# MPU6050.net
KiCad netlist of a schematic drawn in EAGLE
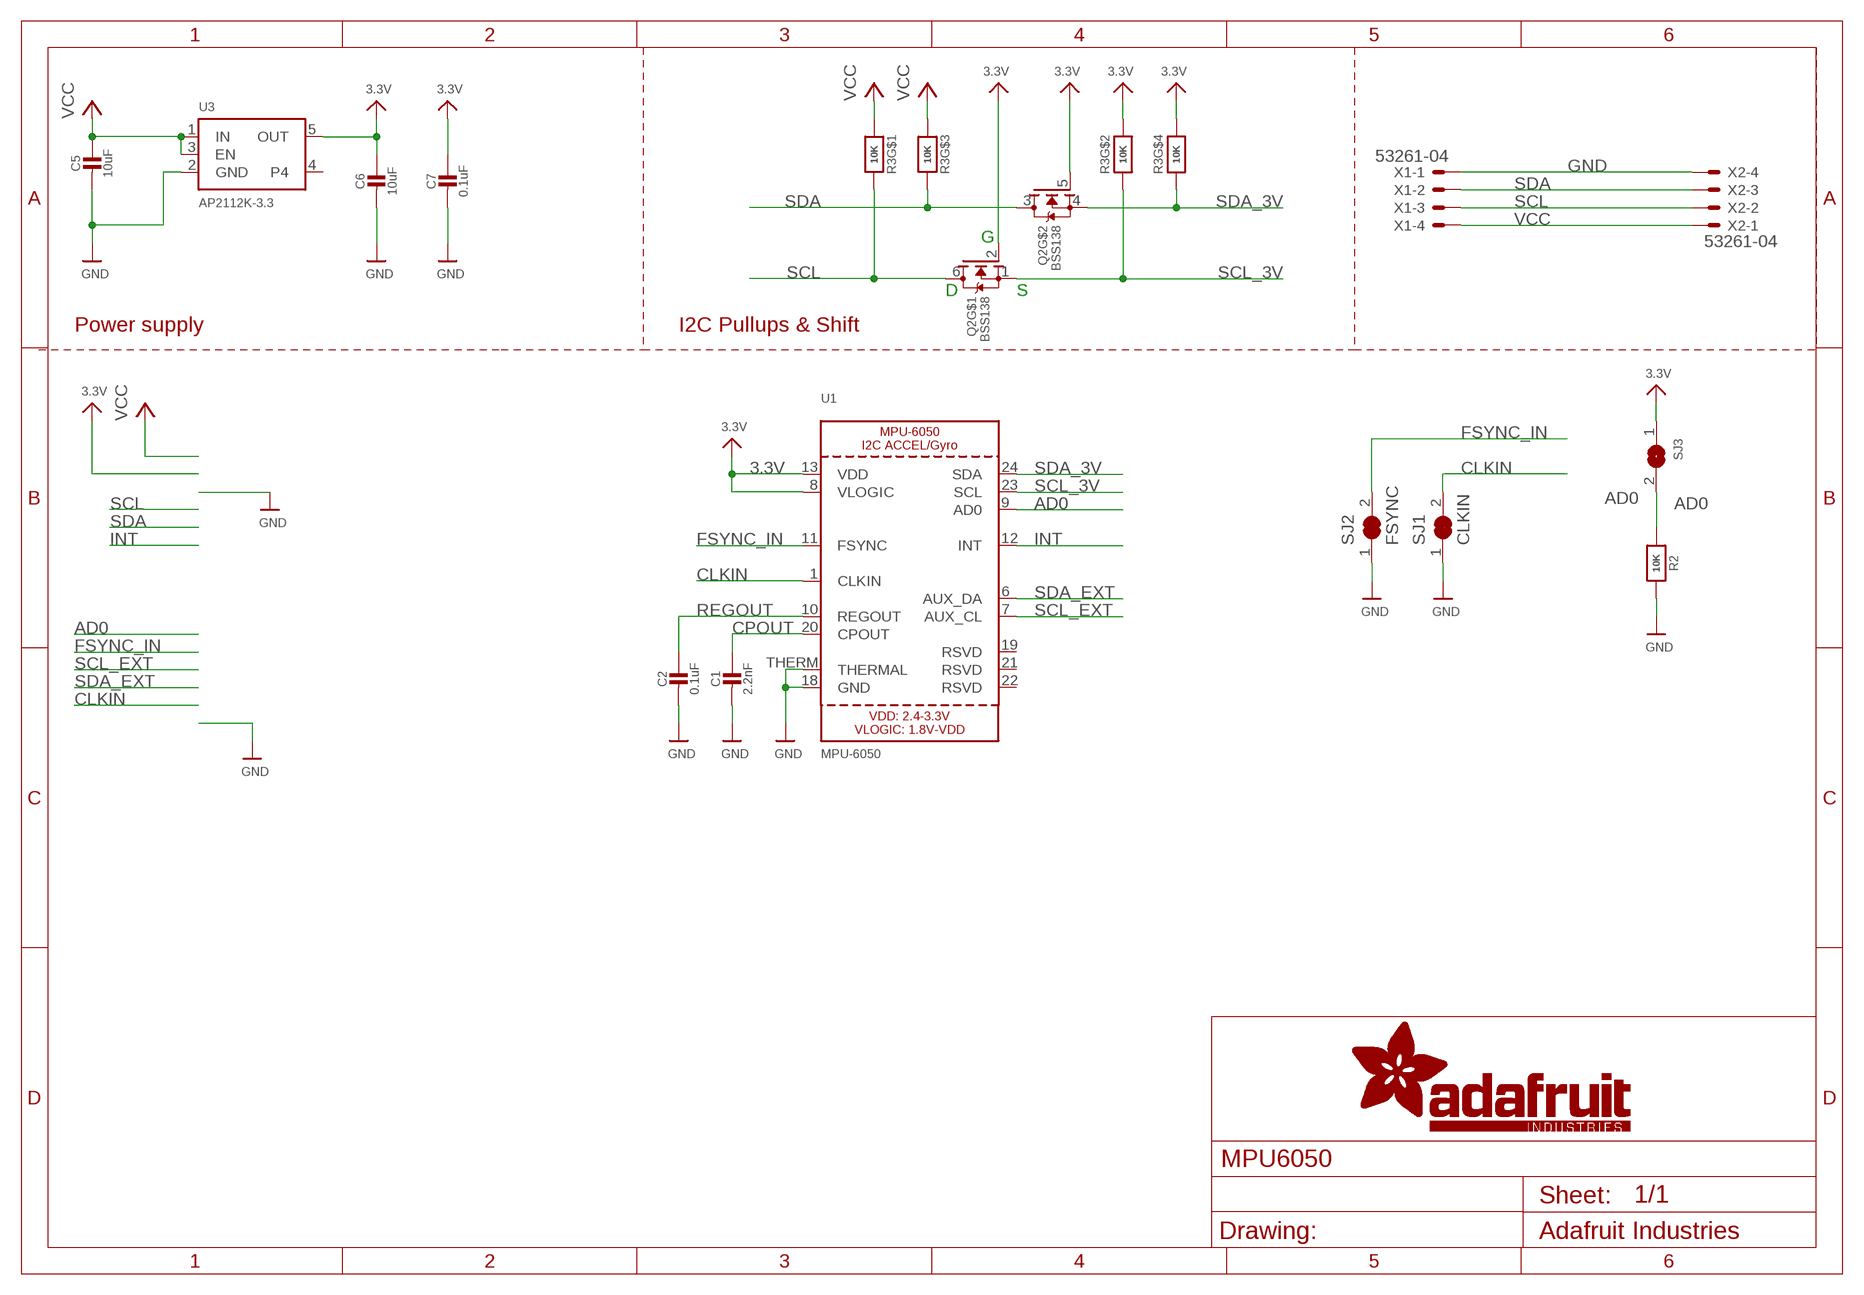
[diagram p0: schematic, sheet 1]

(export (version "E")
  (design (tool "Eeschema 10.0.6"))
  (components
    (comp (ref "C1")
      (value "2.2nF")
      (footprint "eagle-import:0603-NO")
      (libsource (lib "eagle-import") (part "CAP_CERAMIC0603_NO"))
    )
    (comp (ref "C2")
      (value "0.1uF")
      (footprint "eagle-import:0603-NO")
      (libsource (lib "eagle-import") (part "CAP_CERAMIC0603_NO"))
    )
    (comp (ref "C5")
      (value "10uF")
      (footprint "eagle-import:0805-NO")
      (libsource (lib "eagle-import") (part "CAP_CERAMIC0805-NOOUTLINE"))
    )
    (comp (ref "C6")
      (value "10uF")
      (footprint "eagle-import:0805-NO")
      (libsource (lib "eagle-import") (part "CAP_CERAMIC0805-NOOUTLINE"))
    )
    (comp (ref "C7")
      (value "0.1uF")
      (footprint "eagle-import:0603-NO")
      (libsource (lib "eagle-import") (part "CAP_CERAMIC0603_NO"))
    )
    (comp (ref "Q2")
      (value "BSS138")
      (footprint "eagle-import:SOT363")
      (libsource (lib "eagle-import") (part "MOSFET-N_DUAL"))
    )
    (comp (ref "R2")
      (value "10K")
      (footprint "eagle-import:0603-NO")
      (libsource (lib "eagle-import") (part "RESISTOR_0603_NOOUT"))
    )
    (comp (ref "R3")
      (value "10K")
      (footprint "eagle-import:RESPACK_4X0603")
      (libsource (lib "eagle-import") (part "RESISTOR_4PACK"))
    )
    (comp (ref "SJ1")
      (value "CLKIN")
      (footprint "eagle-import:SOLDERJUMPER_CLOSEDWIRE")
      (libsource (lib "eagle-import") (part "SOLDERJUMPER_CLOSED"))
    )
    (comp (ref "SJ2")
      (value "FSYNC")
      (footprint "eagle-import:SOLDERJUMPER_CLOSEDWIRE")
      (libsource (lib "eagle-import") (part "SOLDERJUMPER_CLOSED"))
    )
    (comp (ref "SJ3")
      (value "SOLDERJUMPER")
      (footprint "eagle-import:SOLDERJUMPER_ARROW_NOPASTE")
      (libsource (lib "eagle-import") (part "SOLDERJUMPER"))
    )
    (comp (ref "U1")
      (value "MPU-6050")
      (footprint "eagle-import:QFN24_4MM_SMSC")
      (libsource (lib "eagle-import") (part "MPU-6050"))
    )
    (comp (ref "U3")
      (value "AP2112K-3.3")
      (footprint "eagle-import:SOT23-5")
      (libsource (lib "eagle-import") (part "VREG_SOT23-5"))
    )
    (comp (ref "X1")
      (value "53261-04")
      (footprint "eagle-import:53261-04")
      (fields (field (name "MF") "MOLEX"))
      (libsource (lib "eagle-import") (part "53?-04261"))
    )
    (comp (ref "X2")
      (value "53261-04")
      (footprint "eagle-import:53261-04")
      (fields (field (name "MF") "MOLEX"))
      (libsource (lib "eagle-import") (part "53?-04261"))
    )
  )
  (nets
    (net (code "1") (name "/AD0") (class "Default")
      (node (ref "R2") (pin "1") (pinfunction "1_1") (pintype "passive"))
      (node (ref "SJ3") (pin "2") (pinfunction "2_2") (pintype "passive"))
      (node (ref "U1") (pin "9") (pinfunction "AD0_9") (pintype "input"))
    )
    (net (code "2") (name "/CLKIN") (class "Default")
      (node (ref "SJ1") (pin "2") (pinfunction "2_2") (pintype "passive"))
      (node (ref "U1") (pin "1") (pinfunction "CLKIN_1") (pintype "input"))
    )
    (net (code "3") (name "/CPOUT") (class "Default")
      (node (ref "C1") (pin "1") (pinfunction "1_1") (pintype "passive"))
      (node (ref "U1") (pin "20") (pinfunction "CPOUT_20") (pintype "passive"))
    )
    (net (code "4") (name "/FSYNC_IN") (class "Default")
      (node (ref "SJ2") (pin "2") (pinfunction "2_2") (pintype "passive"))
      (node (ref "U1") (pin "11") (pinfunction "FSYNC_11") (pintype "input"))
    )
    (net (code "5") (name "/INT") (class "Default")
      (node (ref "U1") (pin "12") (pinfunction "INT_12") (pintype "output"))
    )
    (net (code "6") (name "/REGOUT") (class "Default")
      (node (ref "C2") (pin "1") (pinfunction "1_1") (pintype "passive"))
      (node (ref "U1") (pin "10") (pinfunction "REGOUT_10") (pintype "passive"))
    )
    (net (code "7") (name "/SCL") (class "Default")
      (node (ref "Q2") (pin "6") (pinfunction "D_6") (pintype "bidirectional"))
      (node (ref "R3") (pin "8") (pinfunction "2_8") (pintype "passive"))
      (node (ref "X1") (pin "3") (pinfunction "S_3") (pintype "passive"))
      (node (ref "X2") (pin "2") (pinfunction "S_2") (pintype "passive"))
    )
    (net (code "8") (name "/SCL_3V") (class "Default")
      (node (ref "Q2") (pin "1") (pinfunction "S_1") (pintype "bidirectional"))
      (node (ref "R3") (pin "7") (pinfunction "2_7") (pintype "passive"))
      (node (ref "U1") (pin "23") (pinfunction "SCL_23") (pintype "bidirectional"))
    )
    (net (code "9") (name "/SCL_EXT") (class "Default")
      (node (ref "U1") (pin "7") (pinfunction "AUX_CL_7") (pintype "bidirectional"))
    )
    (net (code "10") (name "/SDA") (class "Default")
      (node (ref "Q2") (pin "3") (pinfunction "D_3") (pintype "bidirectional"))
      (node (ref "R3") (pin "6") (pinfunction "2_6") (pintype "passive"))
      (node (ref "X1") (pin "2") (pinfunction "S_2") (pintype "passive"))
      (node (ref "X2") (pin "3") (pinfunction "S_3") (pintype "passive"))
    )
    (net (code "11") (name "/SDA_3V") (class "Default")
      (node (ref "Q2") (pin "4") (pinfunction "S_4") (pintype "bidirectional"))
      (node (ref "R3") (pin "5") (pinfunction "2_5") (pintype "passive"))
      (node (ref "U1") (pin "24") (pinfunction "SDA_24") (pintype "bidirectional"))
    )
    (net (code "12") (name "/SDA_EXT") (class "Default")
      (node (ref "U1") (pin "6") (pinfunction "AUX_DA_6") (pintype "bidirectional"))
    )
    (net (code "13") (name "3.3V") (class "Default")
      (node (ref "C6") (pin "1") (pinfunction "1_1") (pintype "passive"))
      (node (ref "C7") (pin "1") (pinfunction "1_1") (pintype "passive"))
      (node (ref "Q2") (pin "2") (pinfunction "G_2") (pintype "bidirectional"))
      (node (ref "Q2") (pin "5") (pinfunction "G_5") (pintype "bidirectional"))
      (node (ref "R3") (pin "2") (pinfunction "1_2") (pintype "passive"))
      (node (ref "R3") (pin "4") (pinfunction "1_4") (pintype "passive"))
      (node (ref "SJ3") (pin "1") (pinfunction "1_1") (pintype "passive"))
      (node (ref "U1") (pin "13") (pinfunction "VDD_13") (pintype "power_in"))
      (node (ref "U1") (pin "8") (pinfunction "VLOGIC_8") (pintype "power_in"))
      (node (ref "U3") (pin "5") (pinfunction "OUT_5") (pintype "power_in"))
    )
    (net (code "14") (name "GND") (class "Default")
      (node (ref "C1") (pin "2") (pinfunction "2_2") (pintype "passive"))
      (node (ref "C2") (pin "2") (pinfunction "2_2") (pintype "passive"))
      (node (ref "C5") (pin "2") (pinfunction "2_2") (pintype "passive"))
      (node (ref "C6") (pin "2") (pinfunction "2_2") (pintype "passive"))
      (node (ref "C7") (pin "2") (pinfunction "2_2") (pintype "passive"))
      (node (ref "R2") (pin "2") (pinfunction "2_2") (pintype "passive"))
      (node (ref "SJ1") (pin "1") (pinfunction "1_1") (pintype "passive"))
      (node (ref "SJ2") (pin "1") (pinfunction "1_1") (pintype "passive"))
      (node (ref "U1") (pin "18") (pinfunction "GND_18") (pintype "power_in"))
      (node (ref "U1") (pin "THERM") (pinfunction "THERMAL_THERM") (pintype "power_in"))
      (node (ref "U3") (pin "2") (pinfunction "GND_2") (pintype "power_in"))
      (node (ref "X1") (pin "1") (pinfunction "S_1") (pintype "passive"))
      (node (ref "X2") (pin "4") (pinfunction "S_4") (pintype "passive"))
    )
    (net (code "15") (name "VCC") (class "Default")
      (node (ref "C5") (pin "1") (pinfunction "1_1") (pintype "passive"))
      (node (ref "R3") (pin "1") (pinfunction "1_1") (pintype "passive"))
      (node (ref "R3") (pin "3") (pinfunction "1_3") (pintype "passive"))
      (node (ref "U3") (pin "1") (pinfunction "IN_1") (pintype "power_in"))
      (node (ref "U3") (pin "3") (pinfunction "EN_3") (pintype "input"))
      (node (ref "X1") (pin "4") (pinfunction "S_4") (pintype "passive"))
      (node (ref "X2") (pin "1") (pinfunction "S_1") (pintype "passive"))
    )
    (net (code "16") (name "unconnected-(U1-RSVD-Pad19)") (class "Default")
      (node (ref "U1") (pin "19") (pinfunction "RSVD_19") (pintype "no_connect"))
    )
    (net (code "17") (name "unconnected-(U1-RSVD-Pad21)") (class "Default")
      (node (ref "U1") (pin "21") (pinfunction "RSVD_21") (pintype "no_connect"))
    )
    (net (code "18") (name "unconnected-(U1-RSVD-Pad22)") (class "Default")
      (node (ref "U1") (pin "22") (pinfunction "RSVD_22") (pintype "no_connect"))
    )
    (net (code "19") (name "unconnected-(U3-P4-Pad4)") (class "Default")
      (node (ref "U3") (pin "4") (pinfunction "P4_4") (pintype "bidirectional"))
    )
  )
)
